# beijing_rev_B.net
KiCad netlist of a schematic drawn in EAGLE
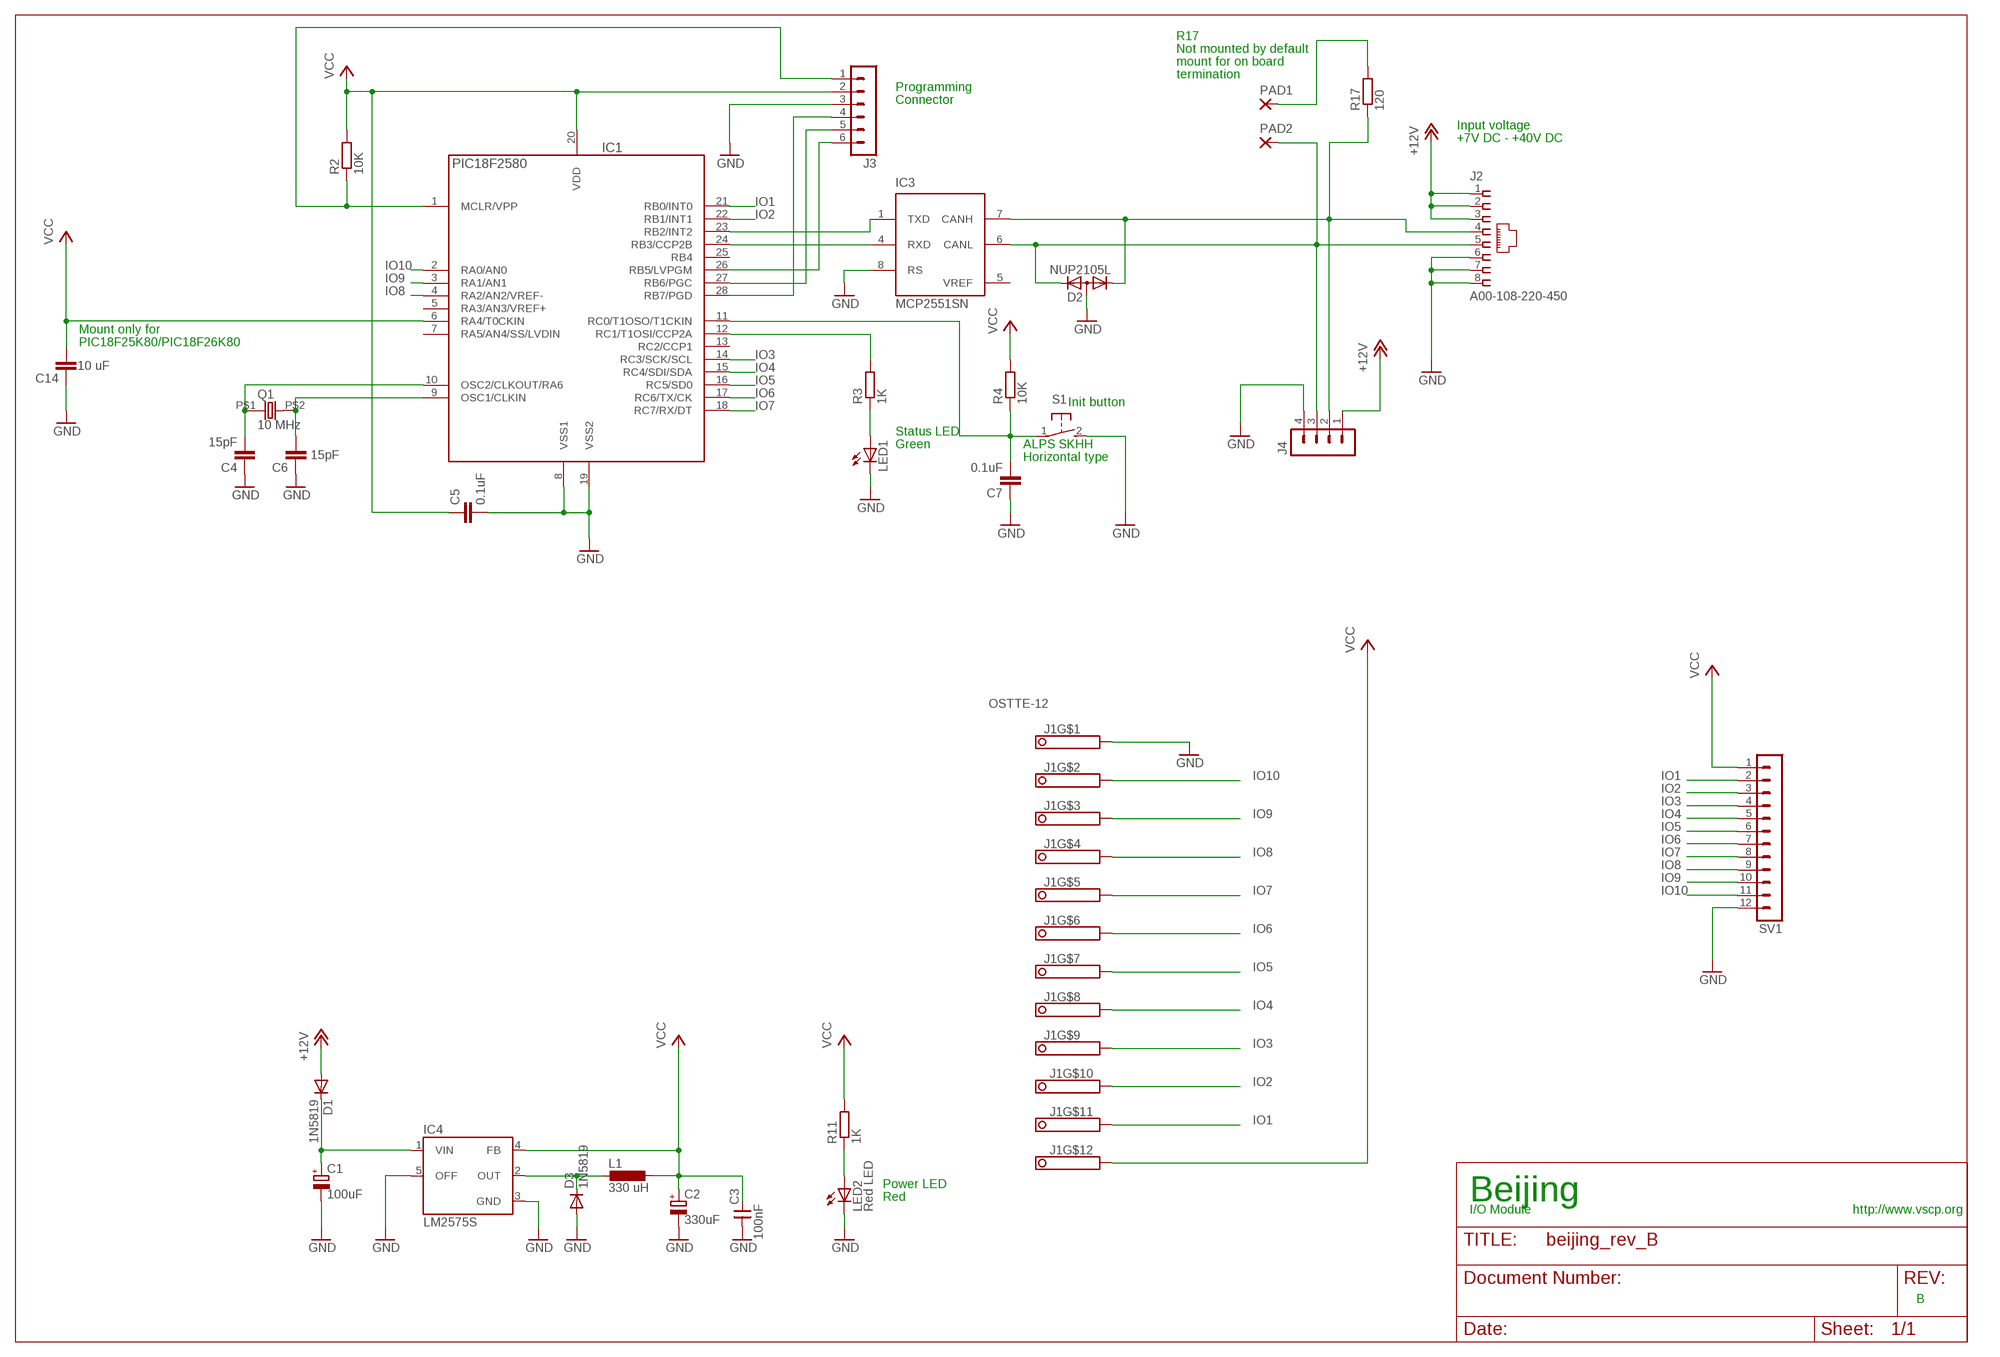
[diagram p0: schematic, sheet 1]

(export (version "E")
  (design (tool "Eeschema 10.0.6"))
  (components
    (comp (ref "C1")
      (value "100uF")
      (footprint "eagle-import:PANASONIC_D")
      (libsource (lib "eagle-import") (part "CPOL-EUD"))
    )
    (comp (ref "C2")
      (value "330uF")
      (footprint "eagle-import:PANASONIC_D")
      (libsource (lib "eagle-import") (part "CPOL-EUD"))
    )
    (comp (ref "C3")
      (value "100nF")
      (footprint "eagle-import:0805")
      (libsource (lib "eagle-import") (part "CNP-0805"))
    )
    (comp (ref "C4")
      (value "15pF")
      (footprint "eagle-import:C0805")
      (libsource (lib "eagle-import") (part "C-EUC0805"))
    )
    (comp (ref "C5")
      (value "0.1uF")
      (footprint "eagle-import:C0805")
      (libsource (lib "eagle-import") (part "C-EUC0805"))
    )
    (comp (ref "C6")
      (value "15pF")
      (footprint "eagle-import:C0805")
      (libsource (lib "eagle-import") (part "C-EUC0805"))
    )
    (comp (ref "C7")
      (value "0.1uF")
      (footprint "eagle-import:C0805")
      (libsource (lib "eagle-import") (part "C-EUC0805"))
    )
    (comp (ref "C14")
      (value "10 uF")
      (footprint "eagle-import:C0805")
      (libsource (lib "eagle-import") (part "C-EUC0805"))
    )
    (comp (ref "D1")
      (value "1N5819")
      (footprint "eagle-import:SOD123")
      (libsource (lib "eagle-import") (part "DIODE-SOD123"))
    )
    (comp (ref "D2")
      (value "NUP2105L")
      (footprint "eagle-import:SOT23")
      (libsource (lib "eagle-import") (part "DIODE-2CA|ACSOT23"))
    )
    (comp (ref "D3")
      (value "1N5819")
      (footprint "eagle-import:SOD123")
      (libsource (lib "eagle-import") (part "DIODE-SOD123"))
    )
    (comp (ref "IC1")
      (value "PIC18F2580")
      (footprint "eagle-import:SO28")
      (libsource (lib "eagle-import") (part "PIC18F252-?I/SOL"))
    )
    (comp (ref "IC3")
      (value "MCP2551SN")
      (footprint "eagle-import:SO-08")
      (libsource (lib "eagle-import") (part "MCP2551SN"))
    )
    (comp (ref "IC4")
      (value "LM2575S")
      (footprint "eagle-import:TO263-5")
      (libsource (lib "eagle-import") (part "LM2575S"))
    )
    (comp (ref "J1")
      (value "OSTTE-12")
      (footprint "eagle-import:PINHEAD-12")
      (libsource (lib "eagle-import") (part "OSTTE-12"))
    )
    (comp (ref "J2")
      (value "A00-108-220-450")
      (footprint "eagle-import:RJ-45")
      (libsource (lib "eagle-import") (part "A00-108-220-450"))
    )
    (comp (ref "J3")
      (value "MA06-1")
      (footprint "eagle-import:MA06-1")
      (libsource (lib "eagle-import") (part "MA06-1"))
    )
    (comp (ref "J4")
      (value "MA04-1")
      (footprint "eagle-import:MA04-1")
      (libsource (lib "eagle-import") (part "MA04-1"))
    )
    (comp (ref "L1")
      (value "330 uH")
      (footprint "eagle-import:DO3316P")
      (libsource (lib "eagle-import") (part "DO3316P"))
    )
    (comp (ref "LED1")
      (value "LEDCHIP-LED0805")
      (footprint "eagle-import:CHIP-LED0805")
      (libsource (lib "eagle-import") (part "LEDCHIP-LED0805"))
    )
    (comp (ref "LED2")
      (value "Red LED")
      (footprint "eagle-import:CHIP-LED0805")
      (libsource (lib "eagle-import") (part "LEDCHIP-LED0805"))
    )
    (comp (ref "PAD1")
      (value "1,6/0,8")
      (footprint "eagle-import:1,6_0,8")
      (libsource (lib "eagle-import") (part "1,6/0,8"))
    )
    (comp (ref "PAD2")
      (value "1,6/0,8")
      (footprint "eagle-import:1,6_0,8")
      (libsource (lib "eagle-import") (part "1,6/0,8"))
    )
    (comp (ref "Q1")
      (value "10 MHz")
      (footprint "eagle-import:9C")
      (libsource (lib "eagle-import") (part "HC-49S"))
    )
    (comp (ref "R2")
      (value "10K")
      (footprint "eagle-import:R0805")
      (libsource (lib "eagle-import") (part "R-EU_R0805"))
    )
    (comp (ref "R3")
      (value "1K")
      (footprint "eagle-import:R0805")
      (libsource (lib "eagle-import") (part "R-EU_R0805"))
    )
    (comp (ref "R4")
      (value "10K")
      (footprint "eagle-import:R0805")
      (libsource (lib "eagle-import") (part "R-EU_R0805"))
    )
    (comp (ref "R11")
      (value "1K")
      (footprint "eagle-import:R0805")
      (libsource (lib "eagle-import") (part "R-EU_R0805"))
    )
    (comp (ref "R17")
      (value "120")
      (footprint "eagle-import:R0805")
      (libsource (lib "eagle-import") (part "R-EU_R0805"))
    )
    (comp (ref "S1")
      (value "31-XX")
      (footprint "eagle-import:B3F-31XX")
      (fields (field (name "MPN") "B3F-3100"))
      (libsource (lib "eagle-import") (part "31-XX"))
    )
    (comp (ref "SV1")
      (value "MA12-1")
      (footprint "eagle-import:MA12-1")
      (libsource (lib "eagle-import") (part "MA12-1"))
    )
  )
  (nets
    (net (code "1") (name "+12V") (class "Default")
      (node (ref "D1") (pin "A") (pinfunction "A_A") (pintype "passive"))
      (node (ref "J2") (pin "1") (pinfunction "1_1") (pintype "passive"))
      (node (ref "J2") (pin "2") (pinfunction "2_2") (pintype "passive"))
      (node (ref "J2") (pin "3") (pinfunction "3_3") (pintype "passive"))
      (node (ref "J4") (pin "1") (pinfunction "1_1") (pintype "passive"))
    )
    (net (code "2") (name "/IO1") (class "Default")
      (node (ref "IC1") (pin "21") (pinfunction "RB0/INT0_21") (pintype "bidirectional"))
      (node (ref "J1") (pin "11") (pinfunction "K_11") (pintype "passive"))
      (node (ref "SV1") (pin "2") (pinfunction "2_2") (pintype "passive"))
    )
    (net (code "3") (name "/IO2") (class "Default")
      (node (ref "IC1") (pin "22") (pinfunction "RB1/INT1_22") (pintype "bidirectional"))
      (node (ref "J1") (pin "10") (pinfunction "K_10") (pintype "passive"))
      (node (ref "SV1") (pin "3") (pinfunction "3_3") (pintype "passive"))
    )
    (net (code "4") (name "/IO3") (class "Default")
      (node (ref "IC1") (pin "14") (pinfunction "RC3/SCK/SCL_14") (pintype "bidirectional"))
      (node (ref "J1") (pin "9") (pinfunction "K_9") (pintype "passive"))
      (node (ref "SV1") (pin "4") (pinfunction "4_4") (pintype "passive"))
    )
    (net (code "5") (name "/IO4") (class "Default")
      (node (ref "IC1") (pin "15") (pinfunction "RC4/SDI/SDA_15") (pintype "bidirectional"))
      (node (ref "J1") (pin "8") (pinfunction "K_8") (pintype "passive"))
      (node (ref "SV1") (pin "5") (pinfunction "5_5") (pintype "passive"))
    )
    (net (code "6") (name "/IO5") (class "Default")
      (node (ref "IC1") (pin "16") (pinfunction "RC5/SD0_16") (pintype "bidirectional"))
      (node (ref "J1") (pin "7") (pinfunction "K_7") (pintype "passive"))
      (node (ref "SV1") (pin "6") (pinfunction "6_6") (pintype "passive"))
    )
    (net (code "7") (name "/IO6") (class "Default")
      (node (ref "IC1") (pin "17") (pinfunction "RC6/TX/CK_17") (pintype "bidirectional"))
      (node (ref "J1") (pin "6") (pinfunction "K_6") (pintype "passive"))
      (node (ref "SV1") (pin "7") (pinfunction "7_7") (pintype "passive"))
    )
    (net (code "8") (name "/IO7") (class "Default")
      (node (ref "IC1") (pin "18") (pinfunction "RC7/RX/DT_18") (pintype "bidirectional"))
      (node (ref "J1") (pin "5") (pinfunction "K_5") (pintype "passive"))
      (node (ref "SV1") (pin "8") (pinfunction "8_8") (pintype "passive"))
    )
    (net (code "9") (name "/IO8") (class "Default")
      (node (ref "IC1") (pin "4") (pinfunction "RA2/AN2/VREF-_4") (pintype "bidirectional"))
      (node (ref "J1") (pin "4") (pinfunction "K_4") (pintype "passive"))
      (node (ref "SV1") (pin "9") (pinfunction "9_9") (pintype "passive"))
    )
    (net (code "10") (name "/IO9") (class "Default")
      (node (ref "IC1") (pin "3") (pinfunction "RA1/AN1_3") (pintype "bidirectional"))
      (node (ref "J1") (pin "3") (pinfunction "K_3") (pintype "passive"))
      (node (ref "SV1") (pin "10") (pinfunction "10_10") (pintype "passive"))
    )
    (net (code "11") (name "/IO10") (class "Default")
      (node (ref "IC1") (pin "2") (pinfunction "RA0/AN0_2") (pintype "bidirectional"))
      (node (ref "J1") (pin "2") (pinfunction "K_2") (pintype "passive"))
      (node (ref "SV1") (pin "11") (pinfunction "11_11") (pintype "passive"))
    )
    (net (code "12") (name "/VREF") (class "Default")
      (node (ref "IC3") (pin "5") (pinfunction "VREF_5") (pintype "power_in"))
    )
    (net (code "13") (name "GND") (class "Default")
      (node (ref "C1") (pin "-") (pinfunction "-_-") (pintype "passive"))
      (node (ref "C14") (pin "1") (pinfunction "1_1") (pintype "passive"))
      (node (ref "C2") (pin "-") (pinfunction "-_-") (pintype "passive"))
      (node (ref "C3") (pin "1") (pinfunction "1_1") (pintype "passive"))
      (node (ref "C4") (pin "1") (pinfunction "1_1") (pintype "passive"))
      (node (ref "C5") (pin "2") (pinfunction "2_2") (pintype "passive"))
      (node (ref "C6") (pin "1") (pinfunction "1_1") (pintype "passive"))
      (node (ref "C7") (pin "1") (pinfunction "1_1") (pintype "passive"))
      (node (ref "D2") (pin "3") (pinfunction "A_3") (pintype "passive"))
      (node (ref "D3") (pin "A") (pinfunction "A_A") (pintype "passive"))
      (node (ref "IC1") (pin "19") (pinfunction "VSS2_19") (pintype "power_in"))
      (node (ref "IC1") (pin "8") (pinfunction "VSS1_8") (pintype "power_in"))
      (node (ref "IC3") (pin "8") (pinfunction "RS_8") (pintype "input"))
      (node (ref "IC4") (pin "3") (pinfunction "GND_3") (pintype "power_in"))
      (node (ref "IC4") (pin "5") (pinfunction "OFF_5") (pintype "input"))
      (node (ref "J1") (pin "1") (pinfunction "K_1") (pintype "passive"))
      (node (ref "J2") (pin "6") (pinfunction "6_6") (pintype "passive"))
      (node (ref "J2") (pin "7") (pinfunction "7_7") (pintype "passive"))
      (node (ref "J2") (pin "8") (pinfunction "8_8") (pintype "passive"))
      (node (ref "J3") (pin "3") (pinfunction "3_3") (pintype "passive"))
      (node (ref "J4") (pin "4") (pinfunction "4_4") (pintype "passive"))
      (node (ref "LED1") (pin "C") (pinfunction "C_C") (pintype "passive"))
      (node (ref "LED2") (pin "C") (pinfunction "C_C") (pintype "passive"))
      (node (ref "S1") (pin "2") (pinfunction "S_2") (pintype "passive"))
      (node (ref "SV1") (pin "12") (pinfunction "12_12") (pintype "passive"))
    )
    (net (code "14") (name "Net-(D2-K1)") (class "Default")
      (node (ref "D2") (pin "1") (pinfunction "K1_1") (pintype "passive"))
      (node (ref "IC3") (pin "7") (pinfunction "CANH_7") (pintype "bidirectional"))
      (node (ref "J2") (pin "4") (pinfunction "4_4") (pintype "passive"))
      (node (ref "J4") (pin "2") (pinfunction "2_2") (pintype "passive"))
      (node (ref "R17") (pin "1") (pinfunction "1_1") (pintype "passive"))
    )
    (net (code "15") (name "Net-(D2-K2)") (class "Default")
      (node (ref "D2") (pin "2") (pinfunction "K2_2") (pintype "passive"))
      (node (ref "IC3") (pin "6") (pinfunction "CANL_6") (pintype "bidirectional"))
      (node (ref "J2") (pin "5") (pinfunction "5_5") (pintype "passive"))
      (node (ref "J4") (pin "3") (pinfunction "3_3") (pintype "passive"))
      (node (ref "PAD2") (pin "1") (pinfunction "P_1") (pintype "passive"))
    )
    (net (code "16") (name "Net-(IC1-MCLR{slash}VPP)") (class "Default")
      (node (ref "IC1") (pin "1") (pinfunction "MCLR/VPP_1") (pintype "input"))
      (node (ref "J3") (pin "1") (pinfunction "1_1") (pintype "passive"))
      (node (ref "R2") (pin "1") (pinfunction "1_1") (pintype "passive"))
    )
    (net (code "17") (name "Net-(IC1-OSC1{slash}CLKIN)") (class "Default")
      (node (ref "C6") (pin "2") (pinfunction "2_2") (pintype "passive"))
      (node (ref "IC1") (pin "9") (pinfunction "OSC1/CLKIN_9") (pintype "input"))
      (node (ref "Q1") (pin "P$2") (pinfunction "2_P$2") (pintype "passive"))
    )
    (net (code "18") (name "Net-(IC1-OSC2{slash}CLKOUT{slash}RA6)") (class "Default")
      (node (ref "C4") (pin "2") (pinfunction "2_2") (pintype "passive"))
      (node (ref "IC1") (pin "10") (pinfunction "OSC2/CLKOUT/RA6_10") (pintype "output"))
      (node (ref "Q1") (pin "P$1") (pinfunction "1_P$1") (pintype "passive"))
    )
    (net (code "19") (name "Net-(IC1-RB2{slash}INT2)") (class "Default")
      (node (ref "IC1") (pin "23") (pinfunction "RB2/INT2_23") (pintype "bidirectional"))
      (node (ref "IC3") (pin "1") (pinfunction "TXD_1") (pintype "input"))
    )
    (net (code "20") (name "Net-(IC1-RB3{slash}CCP2B)") (class "Default")
      (node (ref "IC1") (pin "24") (pinfunction "RB3/CCP2B_24") (pintype "bidirectional"))
      (node (ref "IC3") (pin "4") (pinfunction "RXD_4") (pintype "output"))
    )
    (net (code "21") (name "Net-(IC1-RB5{slash}LVPGM)") (class "Default")
      (node (ref "IC1") (pin "26") (pinfunction "RB5/LVPGM_26") (pintype "bidirectional"))
      (node (ref "J3") (pin "6") (pinfunction "6_6") (pintype "passive"))
    )
    (net (code "22") (name "Net-(IC1-RB6{slash}PGC)") (class "Default")
      (node (ref "IC1") (pin "27") (pinfunction "RB6/PGC_27") (pintype "bidirectional"))
      (node (ref "J3") (pin "5") (pinfunction "5_5") (pintype "passive"))
    )
    (net (code "23") (name "Net-(IC1-RB7{slash}PGD)") (class "Default")
      (node (ref "IC1") (pin "28") (pinfunction "RB7/PGD_28") (pintype "bidirectional"))
      (node (ref "J3") (pin "4") (pinfunction "4_4") (pintype "passive"))
    )
    (net (code "24") (name "Net-(IC1-RC0{slash}T1OSO{slash}T1CKIN)") (class "Default")
      (node (ref "C7") (pin "2") (pinfunction "2_2") (pintype "passive"))
      (node (ref "IC1") (pin "11") (pinfunction "RC0/T1OSO/T1CKIN_11") (pintype "bidirectional"))
      (node (ref "R4") (pin "1") (pinfunction "1_1") (pintype "passive"))
      (node (ref "S1") (pin "1") (pinfunction "P_1") (pintype "passive"))
    )
    (net (code "25") (name "Net-(IC1-RC1{slash}T1OSI{slash}CCP2A)") (class "Default")
      (node (ref "IC1") (pin "12") (pinfunction "RC1/T1OSI/CCP2A_12") (pintype "bidirectional"))
      (node (ref "R3") (pin "2") (pinfunction "2_2") (pintype "passive"))
    )
    (net (code "26") (name "Net-(IC4-OUT)") (class "Default")
      (node (ref "D3") (pin "C") (pinfunction "C_C") (pintype "passive"))
      (node (ref "IC4") (pin "2") (pinfunction "OUT_2") (pintype "output"))
      (node (ref "L1") (pin "1") (pinfunction "1_1") (pintype "passive"))
    )
    (net (code "27") (name "Net-(IC4-VIN)") (class "Default")
      (node (ref "C1") (pin "+") (pinfunction "+_+") (pintype "passive"))
      (node (ref "D1") (pin "C") (pinfunction "C_C") (pintype "passive"))
      (node (ref "IC4") (pin "1") (pinfunction "VIN_1") (pintype "power_in"))
    )
    (net (code "28") (name "Net-(LED1-PadA)") (class "Default")
      (node (ref "LED1") (pin "A") (pinfunction "A_A") (pintype "passive"))
      (node (ref "R3") (pin "1") (pinfunction "1_1") (pintype "passive"))
    )
    (net (code "29") (name "Net-(LED2-PadA)") (class "Default")
      (node (ref "LED2") (pin "A") (pinfunction "A_A") (pintype "passive"))
      (node (ref "R11") (pin "1") (pinfunction "1_1") (pintype "passive"))
    )
    (net (code "30") (name "Net-(PAD1-P)") (class "Default")
      (node (ref "PAD1") (pin "1") (pinfunction "P_1") (pintype "passive"))
      (node (ref "R17") (pin "2") (pinfunction "2_2") (pintype "passive"))
    )
    (net (code "31") (name "VCC") (class "Default")
      (node (ref "C14") (pin "2") (pinfunction "2_2") (pintype "passive"))
      (node (ref "C2") (pin "+") (pinfunction "+_+") (pintype "passive"))
      (node (ref "C3") (pin "2") (pinfunction "2_2") (pintype "passive"))
      (node (ref "C5") (pin "1") (pinfunction "1_1") (pintype "passive"))
      (node (ref "IC1") (pin "20") (pinfunction "VDD_20") (pintype "power_in"))
      (node (ref "IC1") (pin "6") (pinfunction "RA4/T0CKIN_6") (pintype "open_collector"))
      (node (ref "IC4") (pin "4") (pinfunction "FB_4") (pintype "input"))
      (node (ref "J1") (pin "12") (pinfunction "K_12") (pintype "passive"))
      (node (ref "J3") (pin "2") (pinfunction "2_2") (pintype "passive"))
      (node (ref "L1") (pin "2") (pinfunction "2_2") (pintype "passive"))
      (node (ref "R11") (pin "2") (pinfunction "2_2") (pintype "passive"))
      (node (ref "R2") (pin "2") (pinfunction "2_2") (pintype "passive"))
      (node (ref "R4") (pin "2") (pinfunction "2_2") (pintype "passive"))
      (node (ref "SV1") (pin "1") (pinfunction "1_1") (pintype "passive"))
    )
    (net (code "32") (name "unconnected-(IC1-RA3{slash}AN3{slash}VREF+-Pad5)") (class "Default")
      (node (ref "IC1") (pin "5") (pinfunction "RA3/AN3/VREF+_5") (pintype "bidirectional"))
    )
    (net (code "33") (name "unconnected-(IC1-RA5{slash}AN4{slash}SS{slash}LVDIN-Pad7)") (class "Default")
      (node (ref "IC1") (pin "7") (pinfunction "RA5/AN4/SS/LVDIN_7") (pintype "bidirectional"))
    )
    (net (code "34") (name "unconnected-(IC1-RB4-Pad25)") (class "Default")
      (node (ref "IC1") (pin "25") (pinfunction "RB4_25") (pintype "bidirectional"))
    )
    (net (code "35") (name "unconnected-(IC1-RC2{slash}CCP1-Pad13)") (class "Default")
      (node (ref "IC1") (pin "13") (pinfunction "RC2/CCP1_13") (pintype "bidirectional"))
    )
  )
)
